# attiny.net
KiCad netlist of a schematic drawn in EAGLE
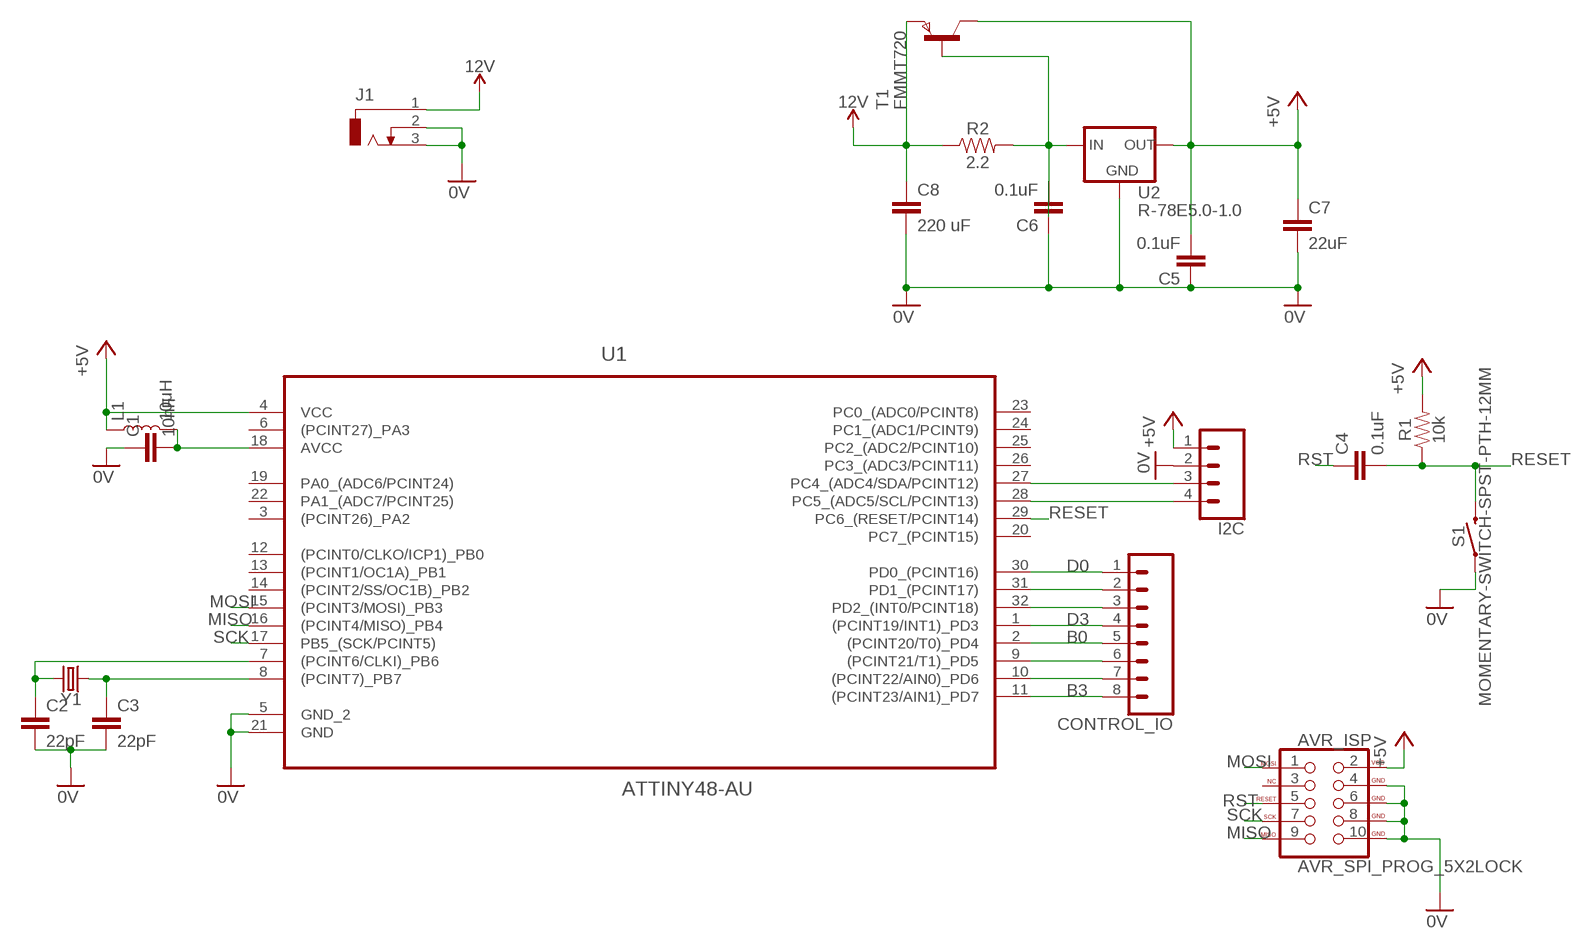
[diagram p0: schematic, sheet 1]

(export (version "E")
  (design (tool "Eeschema 10.0.6"))
  (components
    (comp (ref "AVR_ISP")
      (value "AVR_SPI_PROG_5X2LOCK")
      (footprint "eagle-import:2X5-SHROUDED_LOCK")
      (libsource (lib "eagle-import") (part "AVR_SPI_PROG_5X2LOCK"))
    )
    (comp (ref "C1")
      (value "10nF")
      (footprint "eagle-import:CAP-PTH-10MM")
      (libsource (lib "eagle-import") (part "10NF-PTH-10MM-10000V-1-%"))
    )
    (comp (ref "C2")
      (value "22pF")
      (footprint "eagle-import:0603")
      (libsource (lib "eagle-import") (part "22PF-0603-50V-5%"))
    )
    (comp (ref "C3")
      (value "22pF")
      (footprint "eagle-import:0603")
      (libsource (lib "eagle-import") (part "22PF-0603-50V-5%"))
    )
    (comp (ref "C4")
      (value "0.1uF")
      (footprint "eagle-import:CAP-PTH-SMALL-KIT")
      (libsource (lib "eagle-import") (part "0.1UF-KIT-EZ-50V-20%"))
    )
    (comp (ref "C5")
      (value "0.1uF")
      (footprint "eagle-import:CAP-PTH-SMALL-KIT")
      (libsource (lib "eagle-import") (part "0.1UF-KIT-EZ-50V-20%"))
    )
    (comp (ref "C6")
      (value "0.1uF")
      (footprint "eagle-import:CAP-PTH-SMALL-KIT")
      (libsource (lib "eagle-import") (part "0.1UF-KIT-EZ-50V-20%"))
    )
    (comp (ref "C7")
      (value "22uF")
      (footprint "eagle-import:0805")
      (libsource (lib "eagle-import") (part "22UF-0805-6.3V-20%"))
    )
    (comp (ref "C8")
      (value "220 uF")
      (footprint "eagle-import:C7.5B5")
      (libsource (lib "eagle-import") (part "C7.5/5"))
    )
    (comp (ref "CONTROL_IO")
      (value "CONN_08\"")
      (footprint "eagle-import:1X08")
      (libsource (lib "eagle-import") (part "CONN_08{dblquote}"))
    )
    (comp (ref "I2C")
      (value "CONN_04PTH")
      (footprint "eagle-import:1X04")
      (libsource (lib "eagle-import") (part "CONN_04PTH"))
    )
    (comp (ref "J1")
      (value "DCJ0303")
      (footprint "eagle-import:DCJ0303")
      (libsource (lib "eagle-import") (part "DCJ0303"))
    )
    (comp (ref "L1")
      (value "10μH")
      (footprint "eagle-import:0805")
      (libsource (lib "eagle-import") (part "10μH_SHIELDED_INDUCTOR0805"))
    )
    (comp (ref "R1")
      (value "10k")
      (footprint "eagle-import:AXIAL-0.3")
      (libsource (lib "eagle-import") (part "10KOHM-HORIZ-1/6W-5%"))
    )
    (comp (ref "R2")
      (value "2.2")
      (footprint "eagle-import:0603")
      (libsource (lib "eagle-import") (part "2.2OHM-0603-1/10W-5%"))
    )
    (comp (ref "S1")
      (value "MOMENTARY-SWITCH-SPST-PTH-12MM")
      (footprint "eagle-import:TACTILE_SWITCH_PTH_12MM")
      (libsource (lib "eagle-import") (part "MOMENTARY-SWITCH-SPST-PTH-12MM"))
    )
    (comp (ref "T1")
      (value "FMMT720")
      (footprint "eagle-import:SOT-23")
      (libsource (lib "eagle-import") (part "FMMT720"))
    )
    (comp (ref "U1")
      (value "ATTINY48-AU")
      (footprint "eagle-import:QFP80P900X900X120-32N")
      (fields (field (name "MF") "Microchip"))
      (libsource (lib "eagle-import") (part "ATTINY48-AU"))
    )
    (comp (ref "U2")
      (value "R-78E5.0-1.0")
      (footprint "eagle-import:DC-DC_CONVERTER_78XX")
      (libsource (lib "eagle-import") (part "R-78E5.0-1.0"))
    )
    (comp (ref "Y1")
      (value "CRYSTALPTH-2X6")
      (footprint "eagle-import:CRYSTAL-PTH-2X6-CYL")
      (libsource (lib "eagle-import") (part "CRYSTALPTH-2X6"))
    )
  )
  (nets
    (net (code "1") (name "+5V") (class "Default")
      (node (ref "AVR_ISP") (pin "2") (pinfunction "VCC_2") (pintype "power_in"))
      (node (ref "C5") (pin "2") (pinfunction "2_2") (pintype "passive"))
      (node (ref "C7") (pin "1") (pinfunction "1_1") (pintype "passive"))
      (node (ref "I2C") (pin "1") (pinfunction "1_1") (pintype "passive"))
      (node (ref "L1") (pin "1") (pinfunction "1_1") (pintype "passive"))
      (node (ref "R1") (pin "P$2") (pinfunction "2_P$2") (pintype "passive"))
      (node (ref "T1") (pin "1") (pinfunction "C_1") (pintype "passive"))
      (node (ref "U1") (pin "4") (pinfunction "VCC_4") (pintype "power_in"))
      (node (ref "U2") (pin "VOUT") (pinfunction "OUT_VOUT") (pintype "passive"))
    )
    (net (code "2") (name "/B0") (class "Default")
      (node (ref "CONTROL_IO") (pin "5") (pinfunction "5_5") (pintype "passive"))
      (node (ref "U1") (pin "2") (pinfunction "(PCINT20/T0)_PD4_2") (pintype "bidirectional"))
    )
    (net (code "3") (name "/B3") (class "Default")
      (node (ref "CONTROL_IO") (pin "8") (pinfunction "8_8") (pintype "passive"))
      (node (ref "U1") (pin "11") (pinfunction "(PCINT23/AIN1)_PD7_11") (pintype "bidirectional"))
    )
    (net (code "4") (name "/D0") (class "Default")
      (node (ref "CONTROL_IO") (pin "1") (pinfunction "1_1") (pintype "passive"))
      (node (ref "U1") (pin "30") (pinfunction "PD0_(PCINT16)_30") (pintype "bidirectional"))
    )
    (net (code "5") (name "/D3") (class "Default")
      (node (ref "CONTROL_IO") (pin "4") (pinfunction "4_4") (pintype "passive"))
      (node (ref "U1") (pin "1") (pinfunction "(PCINT19/INT1)_PD3_1") (pintype "bidirectional"))
    )
    (net (code "6") (name "/MISO") (class "Default")
      (node (ref "AVR_ISP") (pin "9") (pinfunction "MISO_9") (pintype "passive"))
      (node (ref "U1") (pin "16") (pinfunction "(PCINT4/MISO)_PB4_16") (pintype "bidirectional"))
    )
    (net (code "7") (name "/MOSI") (class "Default")
      (node (ref "AVR_ISP") (pin "1") (pinfunction "MOSI_1") (pintype "passive"))
      (node (ref "U1") (pin "15") (pinfunction "(PCINT3/MOSI)_PB3_15") (pintype "bidirectional"))
    )
    (net (code "8") (name "/RESET") (class "Default")
      (node (ref "C4") (pin "2") (pinfunction "2_2") (pintype "passive"))
      (node (ref "R1") (pin "P$1") (pinfunction "1_P$1") (pintype "passive"))
      (node (ref "S1") (pin "3") (pinfunction "2_3") (pintype "passive"))
      (node (ref "U1") (pin "29") (pinfunction "PC6_(RESET/PCINT14)_29") (pintype "bidirectional"))
    )
    (net (code "9") (name "/RST") (class "Default")
      (node (ref "AVR_ISP") (pin "5") (pinfunction "RESET_5") (pintype "passive"))
      (node (ref "C4") (pin "1") (pinfunction "1_1") (pintype "passive"))
    )
    (net (code "10") (name "/SCK") (class "Default")
      (node (ref "AVR_ISP") (pin "7") (pinfunction "SCK_7") (pintype "passive"))
      (node (ref "U1") (pin "17") (pinfunction "PB5_(SCK/PCINT5)_17") (pintype "bidirectional"))
    )
    (net (code "11") (name "0V") (class "Default")
      (node (ref "AVR_ISP") (pin "10") (pinfunction "GND_10") (pintype "power_in"))
      (node (ref "AVR_ISP") (pin "4") (pinfunction "GND_4") (pintype "power_in"))
      (node (ref "AVR_ISP") (pin "6") (pinfunction "GND_6") (pintype "power_in"))
      (node (ref "AVR_ISP") (pin "8") (pinfunction "GND_8") (pintype "power_in"))
      (node (ref "C1") (pin "1") (pinfunction "1_1") (pintype "passive"))
      (node (ref "C2") (pin "2") (pinfunction "2_2") (pintype "passive"))
      (node (ref "C3") (pin "2") (pinfunction "2_2") (pintype "passive"))
      (node (ref "C5") (pin "1") (pinfunction "1_1") (pintype "passive"))
      (node (ref "C6") (pin "1") (pinfunction "1_1") (pintype "passive"))
      (node (ref "C7") (pin "2") (pinfunction "2_2") (pintype "passive"))
      (node (ref "C8") (pin "2") (pinfunction "2_2") (pintype "passive"))
      (node (ref "I2C") (pin "2") (pinfunction "2_2") (pintype "passive"))
      (node (ref "J1") (pin "2") (pinfunction "2_2") (pintype "passive"))
      (node (ref "J1") (pin "3") (pinfunction "3_3") (pintype "passive"))
      (node (ref "S1") (pin "1") (pinfunction "1_1") (pintype "passive"))
      (node (ref "U1") (pin "21") (pinfunction "GND_21") (pintype "passive"))
      (node (ref "U1") (pin "5") (pinfunction "GND_2_5") (pintype "passive"))
      (node (ref "U2") (pin "GND") (pinfunction "GND_GND") (pintype "input"))
    )
    (net (code "12") (name "12V") (class "Default")
      (node (ref "C8") (pin "1") (pinfunction "1_1") (pintype "passive"))
      (node (ref "J1") (pin "1") (pinfunction "1_1") (pintype "passive"))
      (node (ref "R2") (pin "1") (pinfunction "1_1") (pintype "passive"))
      (node (ref "T1") (pin "2") (pinfunction "E_2") (pintype "passive"))
    )
    (net (code "13") (name "Net-(T1-B)") (class "Default")
      (node (ref "C6") (pin "2") (pinfunction "2_2") (pintype "passive"))
      (node (ref "R2") (pin "2") (pinfunction "2_2") (pintype "passive"))
      (node (ref "T1") (pin "3") (pinfunction "B_3") (pintype "passive"))
      (node (ref "U2") (pin "VIN") (pinfunction "IN_VIN") (pintype "input"))
    )
    (net (code "14") (name "Net-(U1-(PCINT6{slash}CLKI)_PB6)") (class "Default")
      (node (ref "C2") (pin "1") (pinfunction "1_1") (pintype "passive"))
      (node (ref "U1") (pin "7") (pinfunction "(PCINT6/CLKI)_PB6_7") (pintype "bidirectional"))
      (node (ref "Y1") (pin "2") (pinfunction "2_2") (pintype "passive"))
    )
    (net (code "15") (name "Net-(U1-(PCINT7)_PB7)") (class "Default")
      (node (ref "C3") (pin "1") (pinfunction "1_1") (pintype "passive"))
      (node (ref "U1") (pin "8") (pinfunction "(PCINT7)_PB7_8") (pintype "bidirectional"))
      (node (ref "Y1") (pin "1") (pinfunction "1_1") (pintype "passive"))
    )
    (net (code "16") (name "Net-(U1-(PCINT21{slash}T1)_PD5)") (class "Default")
      (node (ref "CONTROL_IO") (pin "6") (pinfunction "6_6") (pintype "passive"))
      (node (ref "U1") (pin "9") (pinfunction "(PCINT21/T1)_PD5_9") (pintype "bidirectional"))
    )
    (net (code "17") (name "Net-(U1-(PCINT22{slash}AIN0)_PD6)") (class "Default")
      (node (ref "CONTROL_IO") (pin "7") (pinfunction "7_7") (pintype "passive"))
      (node (ref "U1") (pin "10") (pinfunction "(PCINT22/AIN0)_PD6_10") (pintype "bidirectional"))
    )
    (net (code "18") (name "Net-(U1-AVCC)") (class "Default")
      (node (ref "C1") (pin "2") (pinfunction "2_2") (pintype "passive"))
      (node (ref "L1") (pin "2") (pinfunction "2_2") (pintype "passive"))
      (node (ref "U1") (pin "18") (pinfunction "AVCC_18") (pintype "power_in"))
    )
    (net (code "19") (name "Net-(U1-PC4_(ADC4{slash}SDA{slash}PCINT12))") (class "Default")
      (node (ref "I2C") (pin "3") (pinfunction "3_3") (pintype "passive"))
      (node (ref "U1") (pin "27") (pinfunction "PC4_(ADC4/SDA/PCINT12)_27") (pintype "bidirectional"))
    )
    (net (code "20") (name "Net-(U1-PC5_(ADC5{slash}SCL{slash}PCINT13))") (class "Default")
      (node (ref "I2C") (pin "4") (pinfunction "4_4") (pintype "passive"))
      (node (ref "U1") (pin "28") (pinfunction "PC5_(ADC5/SCL/PCINT13)_28") (pintype "bidirectional"))
    )
    (net (code "21") (name "Net-(U1-PD1_(PCINT17))") (class "Default")
      (node (ref "CONTROL_IO") (pin "2") (pinfunction "2_2") (pintype "passive"))
      (node (ref "U1") (pin "31") (pinfunction "PD1_(PCINT17)_31") (pintype "bidirectional"))
    )
    (net (code "22") (name "Net-(U1-PD2_(INT0{slash}PCINT18))") (class "Default")
      (node (ref "CONTROL_IO") (pin "3") (pinfunction "3_3") (pintype "passive"))
      (node (ref "U1") (pin "32") (pinfunction "PD2_(INT0/PCINT18)_32") (pintype "bidirectional"))
    )
    (net (code "23") (name "unconnected-(AVR_ISP-NC-Pad3)") (class "Default")
      (node (ref "AVR_ISP") (pin "3") (pinfunction "NC_3") (pintype "no_connect"))
    )
    (net (code "24") (name "unconnected-(U1-(PCINT0{slash}CLKO{slash}ICP1)_PB0-Pad12)") (class "Default")
      (node (ref "U1") (pin "12") (pinfunction "(PCINT0/CLKO/ICP1)_PB0_12") (pintype "bidirectional"))
    )
    (net (code "25") (name "unconnected-(U1-(PCINT1{slash}OC1A)_PB1-Pad13)") (class "Default")
      (node (ref "U1") (pin "13") (pinfunction "(PCINT1/OC1A)_PB1_13") (pintype "bidirectional"))
    )
    (net (code "26") (name "unconnected-(U1-(PCINT2{slash}SS{slash}OC1B)_PB2-Pad14)") (class "Default")
      (node (ref "U1") (pin "14") (pinfunction "(PCINT2/SS/OC1B)_PB2_14") (pintype "bidirectional"))
    )
    (net (code "27") (name "unconnected-(U1-(PCINT26)_PA2-Pad3)") (class "Default")
      (node (ref "U1") (pin "3") (pinfunction "(PCINT26)_PA2_3") (pintype "bidirectional"))
    )
    (net (code "28") (name "unconnected-(U1-(PCINT27)_PA3-Pad6)") (class "Default")
      (node (ref "U1") (pin "6") (pinfunction "(PCINT27)_PA3_6") (pintype "bidirectional"))
    )
    (net (code "29") (name "unconnected-(U1-PA0_(ADC6{slash}PCINT24)-Pad19)") (class "Default")
      (node (ref "U1") (pin "19") (pinfunction "PA0_(ADC6/PCINT24)_19") (pintype "bidirectional"))
    )
    (net (code "30") (name "unconnected-(U1-PA1_(ADC7{slash}PCINT25)-Pad22)") (class "Default")
      (node (ref "U1") (pin "22") (pinfunction "PA1_(ADC7/PCINT25)_22") (pintype "bidirectional"))
    )
    (net (code "31") (name "unconnected-(U1-PC0_(ADC0{slash}PCINT8)-Pad23)") (class "Default")
      (node (ref "U1") (pin "23") (pinfunction "PC0_(ADC0/PCINT8)_23") (pintype "bidirectional"))
    )
    (net (code "32") (name "unconnected-(U1-PC1_(ADC1{slash}PCINT9)-Pad24)") (class "Default")
      (node (ref "U1") (pin "24") (pinfunction "PC1_(ADC1/PCINT9)_24") (pintype "bidirectional"))
    )
    (net (code "33") (name "unconnected-(U1-PC2_(ADC2{slash}PCINT10)-Pad25)") (class "Default")
      (node (ref "U1") (pin "25") (pinfunction "PC2_(ADC2/PCINT10)_25") (pintype "bidirectional"))
    )
    (net (code "34") (name "unconnected-(U1-PC3_(ADC3{slash}PCINT11)-Pad26)") (class "Default")
      (node (ref "U1") (pin "26") (pinfunction "PC3_(ADC3/PCINT11)_26") (pintype "bidirectional"))
    )
    (net (code "35") (name "unconnected-(U1-PC7_(PCINT15)-Pad20)") (class "Default")
      (node (ref "U1") (pin "20") (pinfunction "PC7_(PCINT15)_20") (pintype "bidirectional"))
    )
  )
)
